# P02_Power_Management.net
KiCad netlist of a schematic drawn in Altium Designer
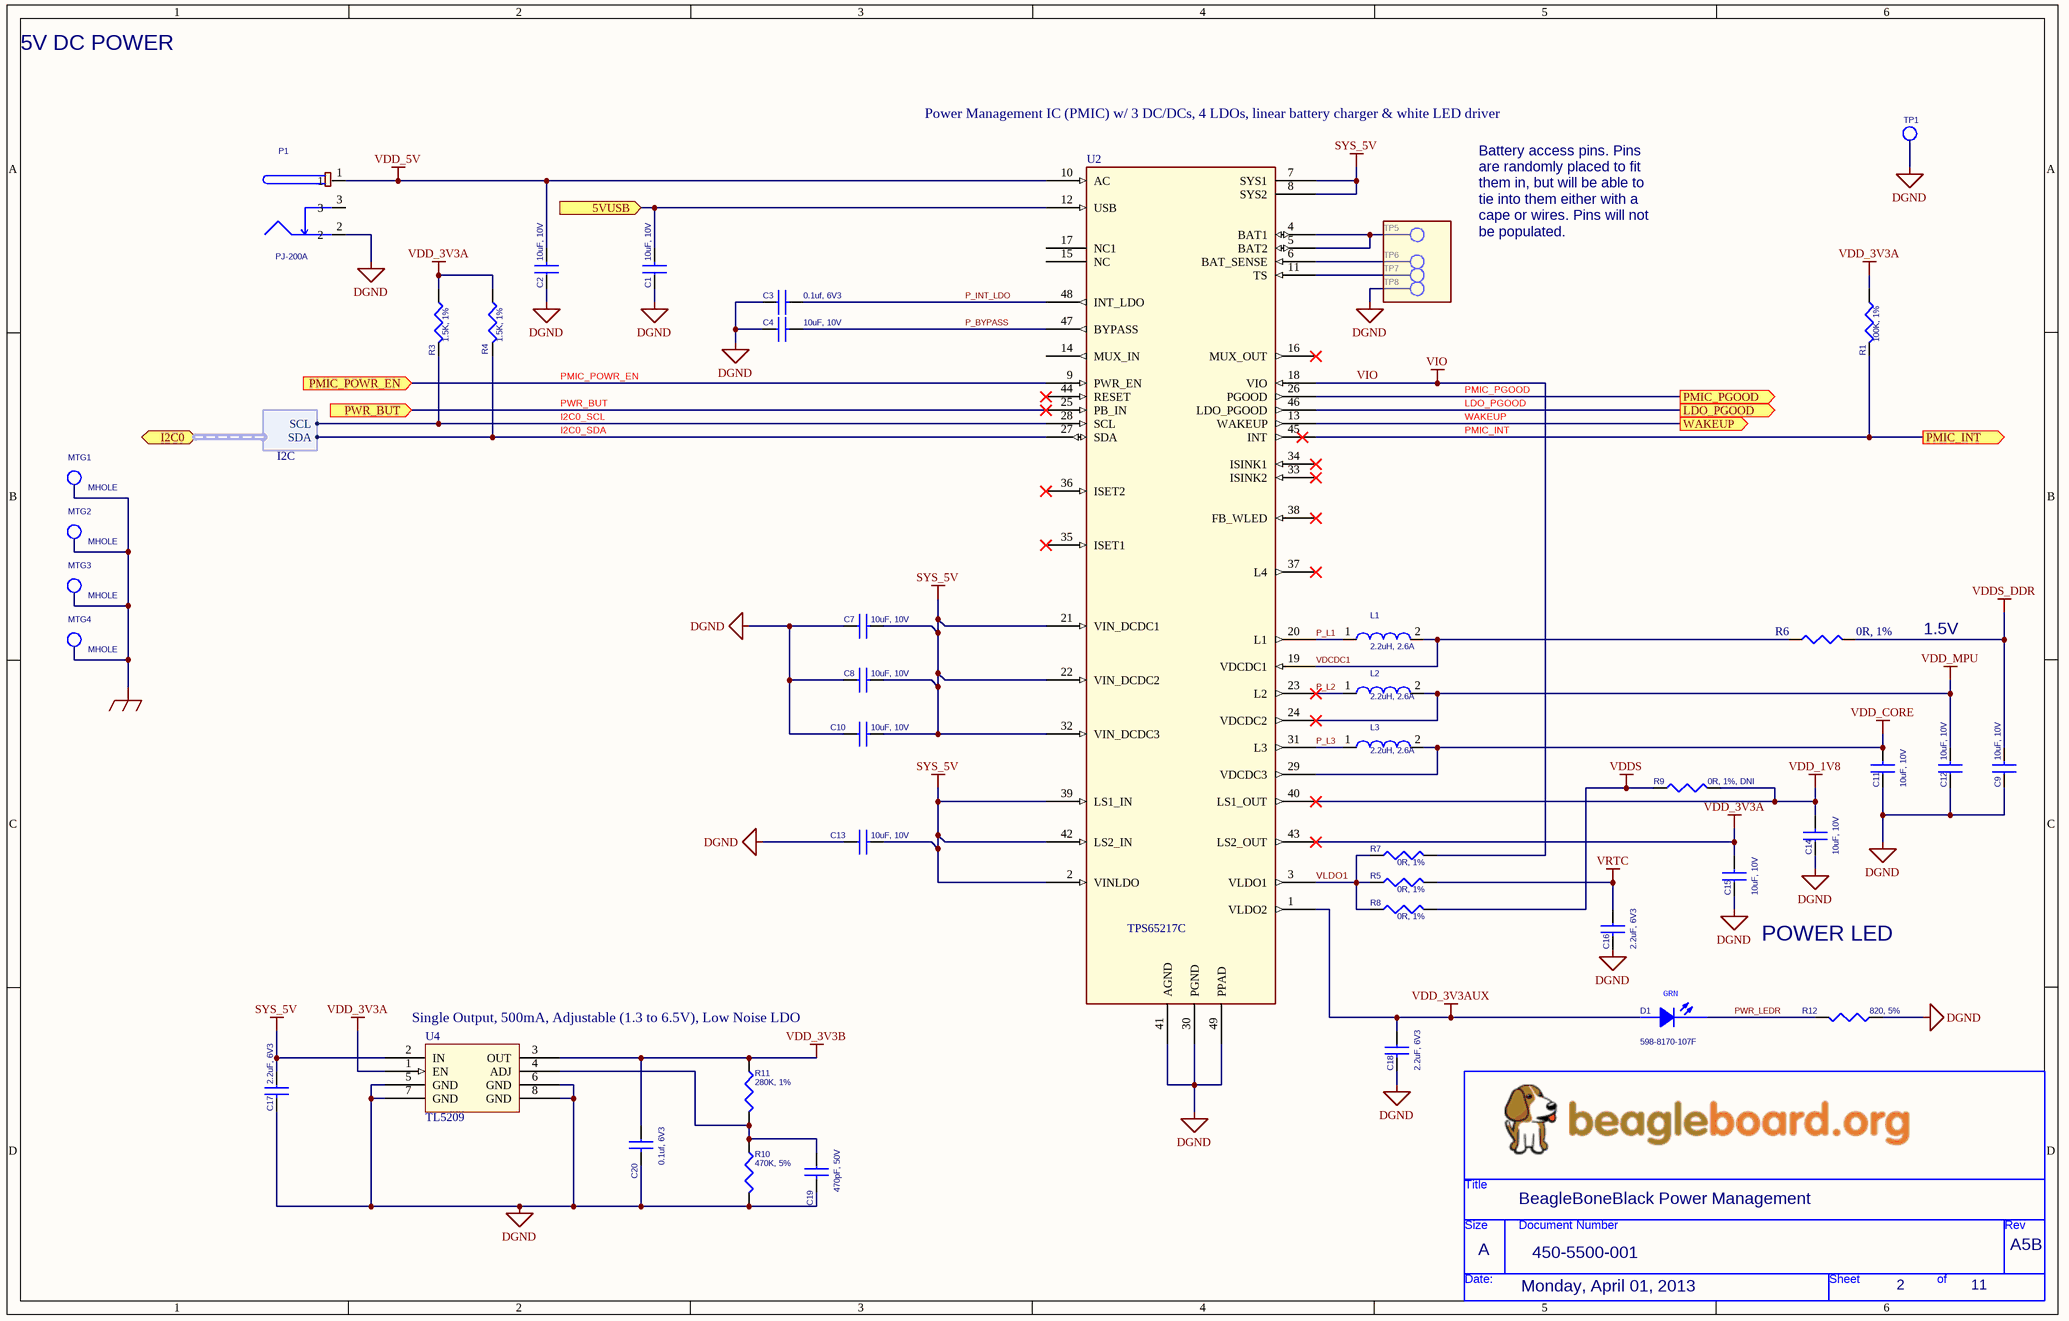
[diagram p0: P02_Power Management.SchDoc]

(export (version "E")
  (design (tool "Eeschema 10.0.6"))
  (components
    (comp (ref "C1")
      (value "10uF, 10V")
      (description "CAP CER 10UF 10V Y5V 0805")
      (fields
        (field (name "MANUFACTURER") "TDK Corporation")
        (field (name "MANUFACTURER PART NUMBER") "C2012Y5V1A106Z")
      )
      (libsource (lib "BEAGLEBONEBLACK_REV A5B") (part "CAP_4.7uF_X5R_6.3V_10%_0603"))
    )
    (comp (ref "C2")
      (value "10uF, 10V")
      (footprint "805")
      (description "CAP CER 10UF 10V Y5V 0805")
      (fields
        (field (name "MANUFACTURER") "TDK Corporation")
        (field (name "MANUFACTURER PART NUMBER") "C2012Y5V1A106Z")
      )
      (libsource (lib "BEAGLEBONEBLACK_REV A5B") (part "CAP_4.7uF_X5R_6.3V_10%_0603"))
    )
    (comp (ref "C3")
      (value "0.1uf, 6V3")
      (footprint "402")
      (description "CAP CER 0.1UF 6.3V 10% X5R 0402")
      (fields
        (field (name "MANUFACTURER") "TDK Corporation")
        (field (name "MANUFACTURER PART NUMBER") "C1005X5R0J104K050BA")
      )
      (libsource (lib "BEAGLEBONEBLACK_REV A5B") (part "CAP_10uF_Y5V_10V_10%_0805"))
    )
    (comp (ref "C4")
      (value "10uF, 10V")
      (description "CAP CER 10UF 10V Y5V 0805")
      (fields
        (field (name "MANUFACTURER") "TDK Corporation")
        (field (name "MANUFACTURER PART NUMBER") "C2012Y5V1A106Z")
      )
      (libsource (lib "BEAGLEBONEBLACK_REV A5B") (part "CAP_10uF_Y5V_10V_10%_0805"))
    )
    (comp (ref "C7")
      (value "10uF, 10V")
      (description "CAP CER 10UF 10V Y5V 0805")
      (fields
        (field (name "MANUFACTURER") "TDK Corporation")
        (field (name "MANUFACTURER PART NUMBER") "C2012Y5V1A106Z")
      )
      (libsource (lib "BEAGLEBONEBLACK_REV A5B") (part "CAP_10uF_Y5V_10V_10%_0805"))
    )
    (comp (ref "C8")
      (value "10uF, 10V")
      (description "CAP CER 10UF 10V Y5V 0805")
      (fields
        (field (name "MANUFACTURER") "TDK Corporation")
        (field (name "MANUFACTURER PART NUMBER") "C2012Y5V1A106Z")
      )
      (libsource (lib "BEAGLEBONEBLACK_REV A5B") (part "CAP_10uF_Y5V_10V_10%_0805"))
    )
    (comp (ref "C9")
      (value "10uF, 10V")
      (description "CAP CER 10UF 10V Y5V 0805")
      (fields
        (field (name "MANUFACTURER") "TDK Corporation")
        (field (name "MANUFACTURER PART NUMBER") "C2012Y5V1A106Z")
      )
      (libsource (lib "BEAGLEBONEBLACK_REV A5B") (part "CAP_10uF_Y5V_10V_10%_0805"))
    )
    (comp (ref "C10")
      (value "10uF, 10V")
      (description "CAP CER 10UF 10V Y5V 0805")
      (fields
        (field (name "MANUFACTURER") "TDK Corporation")
        (field (name "MANUFACTURER PART NUMBER") "C2012Y5V1A106Z")
      )
      (libsource (lib "BEAGLEBONEBLACK_REV A5B") (part "CAP_10uF_Y5V_10V_10%_0805"))
    )
    (comp (ref "C11")
      (value "10uF, 10V")
      (description "CAP CER 10UF 10V Y5V 0805")
      (fields
        (field (name "MANUFACTURER") "TDK Corporation")
        (field (name "MANUFACTURER PART NUMBER") "C2012Y5V1A106Z")
      )
      (libsource (lib "BEAGLEBONEBLACK_REV A5B") (part "CAP_10uF_Y5V_10V_10%_0805"))
    )
    (comp (ref "C12")
      (value "10uF, 10V")
      (description "CAP CER 10UF 10V Y5V 0805")
      (fields
        (field (name "MANUFACTURER") "TDK Corporation")
        (field (name "MANUFACTURER PART NUMBER") "C2012Y5V1A106Z")
      )
      (libsource (lib "BEAGLEBONEBLACK_REV A5B") (part "CAP_10uF_Y5V_10V_10%_0805"))
    )
    (comp (ref "C13")
      (value "10uF, 10V")
      (description "CAP CER 10UF 10V Y5V 0805")
      (fields
        (field (name "MANUFACTURER") "TDK Corporation")
        (field (name "MANUFACTURER PART NUMBER") "C2012Y5V1A106Z")
      )
      (libsource (lib "BEAGLEBONEBLACK_REV A5B") (part "CAP_10uF_Y5V_10V_10%_0805"))
    )
    (comp (ref "C14")
      (value "10uF, 10V")
      (description "CAP CER 10UF 10V Y5V 0805")
      (fields
        (field (name "MANUFACTURER") "TDK Corporation")
        (field (name "MANUFACTURER PART NUMBER") "C2012Y5V1A106Z")
      )
      (libsource (lib "BEAGLEBONEBLACK_REV A5B") (part "CAP_10uF_Y5V_10V_10%_0805"))
    )
    (comp (ref "C15")
      (value "10uF, 10V")
      (description "CAP CER 10UF 10V Y5V 0805")
      (fields
        (field (name "MANUFACTURER") "TDK Corporation")
        (field (name "MANUFACTURER PART NUMBER") "C2012Y5V1A106Z")
      )
      (libsource (lib "BEAGLEBONEBLACK_REV A5B") (part "CAP_10uF_Y5V_10V_10%_0805"))
    )
    (comp (ref "C16")
      (value "2.2uF, 6V3")
      (footprint "402")
      (description "CAP CER 2.2UF 6.3V 10% X5R 0402")
      (fields
        (field (name "MANUFACTURER") "TDK Corporation")
        (field (name "MANUFACTURER PART NUMBER") "C1005X5R0J225K050BC")
      )
      (libsource (lib "BEAGLEBONEBLACK_REV A5B") (part "CAP_2.2uF_X5R_6.3V_10%_0402"))
    )
    (comp (ref "C17")
      (value "2.2uF, 6V3")
      (footprint "402")
      (description "CAP CER 2.2UF 6.3V 10% X5R 0402")
      (fields
        (field (name "MANUFACTURER") "TDK Corporation")
        (field (name "MANUFACTURER PART NUMBER") "C1005X5R0J225K050BC")
      )
      (libsource (lib "BEAGLEBONEBLACK_REV A5B") (part "CAP_2.2uF_X5R_6.3V_10%_0402"))
    )
    (comp (ref "C18")
      (value "2.2uF, 6V3")
      (footprint "402")
      (description "CAP CER 2.2UF 6.3V 10% X5R 0402")
      (fields
        (field (name "MANUFACTURER") "TDK Corporation")
        (field (name "MANUFACTURER PART NUMBER") "C1005X5R0J225K050BC")
      )
      (libsource (lib "BEAGLEBONEBLACK_REV A5B") (part "CAP_2.2uF_X5R_6.3V_10%_0402"))
    )
    (comp (ref "C19")
      (value "470pF, 50V")
      (footprint "402")
      (description "CAP CER 470PF 50V 10% X7R 0402")
      (fields
        (field (name "MANUFACTURER") "Murata Electronics North America")
        (field (name "MANUFACTURER PART NUMBER") "GRM155R71H471KA01D")
      )
      (libsource (lib "BEAGLEBONEBLACK_REV A5B") (part "CAP_2.2uF_X5R_6.3V_10%_0402"))
    )
    (comp (ref "C20")
      (value "0.1uf, 6V3")
      (footprint "402")
      (description "CAP CER 0.1UF 6.3V 10% X5R 0402")
      (fields
        (field (name "MANUFACTURER") "TDK Corporation")
        (field (name "MANUFACTURER PART NUMBER") "C1005X5R0J104K050BA")
      )
      (libsource (lib "BEAGLEBONEBLACK_REV A5B") (part "CAP_0.1uF_X7R_16V_10% 0402"))
    )
    (comp (ref "D1")
      (value "598-8170-107F")
      (footprint "LED_0603")
      (description "LED GREEN CLEAR 0805 SMD")
      (fields
        (field (name "MANUFACTURER") "Lite-On Inc")
        (field (name "MANUFACTURER PART NUMBER") "LTST-C170KGKT")
      )
      (libsource (lib "BEAGLEBONEBLACK_REV A5B") (part "LED_LTST-C150GKT"))
    )
    (comp (ref "L1")
      (value "2.2uH, 2.6A")
      (footprint "2520")
      (description "Inductor 2.2uH smt 2.6A, 58 milliohm")
      (fields
        (field (name "MANUFACTURER") "Murata Electronics North America")
        (field (name "MANUFACTURER PART NUMBER") "LQM2HPN2R2MG0L")
      )
      (libsource (lib "BEAGLEBONEBLACK_REV A5B") (part "IND_2.2uH_2.6A_10%_SMD"))
    )
    (comp (ref "L2")
      (value "2.2uH, 2.6A")
      (footprint "2520")
      (description "INDUCTOR 2.2UH 20% 1300MA 1008")
      (fields (field (name "MFR") "TDK") (field (name "TIINTPARTNUMBER") "1L0025"))
      (libsource (lib "BEAGLEBONEBLACK_REV A5B") (part "IND_2.2uH_2.6A_10%_SMD"))
    )
    (comp (ref "L3")
      (value "2.2uH, 2.6A")
      (footprint "2520")
      (description "INDUCTOR 2.2UH 20% 1300MA 1008")
      (fields (field (name "MFR") "TDK") (field (name "TIINTPARTNUMBER") "1L0025"))
      (libsource (lib "BEAGLEBONEBLACK_REV A5B") (part "IND_2.2uH_2.6A_10%_SMD"))
    )
    (comp (ref "MTG1")
      (value "MHOLE")
      (footprint "MTGH200C125D_PL")
      (libsource (lib "BEAGLEBONEBLACK_REV A5B") (part "MHOLE"))
    )
    (comp (ref "MTG2")
      (value "MHOLE")
      (footprint "MTGH200C125D_PL")
      (libsource (lib "BEAGLEBONEBLACK_REV A5B") (part "MHOLE"))
    )
    (comp (ref "MTG3")
      (value "MHOLE")
      (footprint "MTGH200C125D_PL")
      (libsource (lib "BEAGLEBONEBLACK_REV A5B") (part "MHOLE"))
    )
    (comp (ref "MTG4")
      (value "MHOLE")
      (footprint "MTGH200C125D_PL")
      (libsource (lib "BEAGLEBONEBLACK_REV A5B") (part "MHOLE"))
    )
    (comp (ref "P1")
      (value "PJ-200A")
      (description "CONN PWR JACK 2.1X5.5MM HIGH CUR")
      (fields (field (name "MANUFACTURER") "CUI Inc") (field (name "MANUFACTURER PART NUMBER") "PJ-002AH"))
      (libsource (lib "BEAGLEBONEBLACK_REV A5B") (part "Power_Jack"))
    )
    (comp (ref "R1")
      (value "100K, 1%")
      (footprint "402")
      (description "RES 100K OHM 1/16W 1% 0402 SMD")
      (fields
        (field (name "MANUFACTURER") "Stackpole Electronics Inc")
        (field (name "MANUFACTURER PART NUMBER") "RMCF0402FT100K")
      )
      (libsource (lib "BEAGLEBONEBLACK_REV A5B") (part "RES_100K_1/16W_1%_0402"))
    )
    (comp (ref "R3")
      (value "1.5K, 1%")
      (footprint "402")
      (description "RES 1.50K OHM 1/16W 1% 0402 SMD")
      (fields
        (field (name "MANUFACTURER") "Yageo")
        (field (name "MANUFACTURER PART NUMBER") "RC0402FR-071K5L")
      )
      (libsource (lib "BEAGLEBONEBLACK_REV A5B") (part "RES_1.5K_1/16W_5%_0402"))
    )
    (comp (ref "R4")
      (value "1.5K, 1%")
      (footprint "402")
      (description "RES 1.50K OHM 1/16W 1% 0402 SMD")
      (fields
        (field (name "MANUFACTURER") "Yageo")
        (field (name "MANUFACTURER PART NUMBER") "RC0402FR-071K5L")
      )
      (libsource (lib "BEAGLEBONEBLACK_REV A5B") (part "RES_1.5K_1/16W_5%_0402"))
    )
    (comp (ref "R5")
      (value "0R, 1%")
      (footprint "402")
      (description "RES 0.0 OHM 1/16W 0402 SMD")
      (fields
        (field (name "MANUFACTURER") "Yageo")
        (field (name "MANUFACTURER PART NUMBER") "RC0402JR-070RL")
      )
      (libsource (lib "BEAGLEBONEBLACK_REV A5B") (part "RES_0_1/16W_1%_0402"))
    )
    (comp (ref "R6")
      (value "0R, 1%")
      (footprint "402")
      (description "RES 0.0 OHM 1/16W 0402 SMD")
      (fields
        (field (name "MANUFACTURER") "Yageo")
        (field (name "MANUFACTURER PART NUMBER") "RC0402JR-070RL")
      )
      (libsource (lib "BEAGLEBONEBLACK_REV A5B") (part "RES_0_1/16W_1%_0402"))
    )
    (comp (ref "R7")
      (value "0R, 1%")
      (footprint "402")
      (description "RES 0.0 OHM 1/16W 0402 SMD")
      (fields
        (field (name "MANUFACTURER") "Yageo")
        (field (name "MANUFACTURER PART NUMBER") "RC0402JR-070RL")
      )
      (libsource (lib "BEAGLEBONEBLACK_REV A5B") (part "RES_0_1/16W_1%_0402"))
    )
    (comp (ref "R8")
      (value "0R, 1%")
      (footprint "402")
      (description "RES 0.0 OHM 1/16W 0402 SMD")
      (fields
        (field (name "MANUFACTURER") "Yageo")
        (field (name "MANUFACTURER PART NUMBER") "RC0402JR-070RL")
      )
      (libsource (lib "BEAGLEBONEBLACK_REV A5B") (part "RES_0_1/16W_1%_0402"))
    )
    (comp (ref "R9")
      (value "0R, 1%, DNI")
      (footprint "402")
      (description "RES 0.0 OHM 1/16W 0402 SMD")
      (fields
        (field (name "MANUFACTURER") "Yageo")
        (field (name "MANUFACTURER PART NUMBER") "RC0402JR-070RL")
      )
      (libsource (lib "BEAGLEBONEBLACK_REV A5B") (part "RES_0_1/16W_1%_0402"))
    )
    (comp (ref "R10")
      (value "470K, 5%")
      (footprint "402")
      (description "RES 470K OHM 1/16W 1% 0402 SMD")
      (fields
        (field (name "MANUFACTURER") "Yageo")
        (field (name "MANUFACTURER PART NUMBER") "RC0402FR-07470KL")
      )
      (libsource (lib "BEAGLEBONEBLACK_REV A5B") (part "RES_470_1/10W_5%_0402"))
    )
    (comp (ref "R11")
      (value "280K, 1%")
      (footprint "402")
      (description "RES 280K OHM 1/16W 1% 0402 SMD")
      (fields
        (field (name "MANUFACTURER") "Stackpole Electronics Inc")
        (field (name "MANUFACTURER PART NUMBER") "RMCF0402FT280K")
      )
      (libsource (lib "BEAGLEBONEBLACK_REV A5B") (part "RES_470_1/10W_5%_0402"))
    )
    (comp (ref "R12")
      (value "820, 5%")
      (footprint "402")
      (description "RES 820 OHM 1/10W 5% 0402 SMD")
      (fields
        (field (name "MANUFACTURER") "Yageo")
        (field (name "MANUFACTURER PART NUMBER") "RC0402JR-07820RL")
      )
      (libsource (lib "BEAGLEBONEBLACK_REV A5B") (part "RES_470_1/10W_5%_0402"))
    )
    (comp (ref "TP1")
      (value "TESTPT1")
      (footprint "tp1-8040")
      (libsource (lib "BEAGLEBONEBLACK_REV A5B") (part "TESTPT1"))
    )
    (comp (ref "TP5")
      (value "TESTPT1")
      (footprint "TP60C33D")
      (libsource (lib "BEAGLEBONEBLACK_REV A5B") (part "TESTPT1"))
    )
    (comp (ref "TP6")
      (value "TESTPT1")
      (footprint "TP60C33D")
      (libsource (lib "BEAGLEBONEBLACK_REV A5B") (part "TESTPT1"))
    )
    (comp (ref "TP7")
      (value "TESTPT1")
      (footprint "TP60C33D")
      (libsource (lib "BEAGLEBONEBLACK_REV A5B") (part "TESTPT1"))
    )
    (comp (ref "TP8")
      (value "TESTPT1")
      (footprint "TP60C33D")
      (libsource (lib "BEAGLEBONEBLACK_REV A5B") (part "TESTPT1"))
    )
    (comp (ref "U2")
      (value "TPS65217C")
      (footprint "U_48_RSL")
      (description "IC PMIC BATT PWR SYST 48VQFN")
      (fields
        (field (name "MANUFACTURER") "Texas Instruments")
        (field (name "MANUFACTURER PART NUMBER") "TPS65217CRSLR")
      )
      (libsource (lib "BEAGLEBONEBLACK_REV A5B") (part "PWR_TPS65217_2"))
    )
    (comp (ref "U4")
      (value "TL5209")
      (footprint "SO8-25X75")
      (description "IC LDO VOLT REG 500MA 8-SOIC")
      (fields
        (field (name "MANUFACTURER") "Texas Instruments")
        (field (name "MANUFACTURER PART NUMBER") "TL5209DR")
      )
      (libsource (lib "BEAGLEBONEBLACK_REV A5B") (part "TL5209"))
    )
  )
  (nets
    (net (code "2") (name "/5VUSB") (class "Default")
      (node (ref "C1") (pin "2") (pinfunction "2_2") (pintype "passive"))
      (node (ref "U2") (pin "12") (pinfunction "USB_12") (pintype "input"))
    )
    (net (code "3") (name "/I2C0_SCL") (class "Default")
      (node (ref "R3") (pin "2") (pinfunction "2_2") (pintype "passive"))
      (node (ref "U2") (pin "28") (pinfunction "SCL_28") (pintype "input"))
    )
    (net (code "4") (name "/I2C0_SDA") (class "Default")
      (node (ref "R4") (pin "2") (pinfunction "2_2") (pintype "passive"))
      (node (ref "U2") (pin "27") (pinfunction "SDA_27") (pintype "bidirectional"))
    )
    (net (code "5") (name "/LDO_PGOOD") (class "Default")
      (node (ref "U2") (pin "46") (pinfunction "LDO_PGOOD_46") (pintype "output"))
    )
    (net (code "6") (name "/PMIC_INT") (class "Default")
      (node (ref "R1") (pin "2") (pinfunction "2_2") (pintype "passive"))
      (node (ref "U2") (pin "45") (pinfunction "INT_45") (pintype "output"))
    )
    (net (code "7") (name "/PMIC_PGOOD") (class "Default")
      (node (ref "U2") (pin "26") (pinfunction "PGOOD_26") (pintype "output"))
    )
    (net (code "8") (name "/PMIC_POWR_EN") (class "Default")
      (node (ref "U2") (pin "9") (pinfunction "PWR_EN_9") (pintype "input"))
    )
    (net (code "9") (name "/PWR_BUT") (class "Default")
      (node (ref "U2") (pin "25") (pinfunction "PB_IN_25") (pintype "input+no_connect"))
    )
    (net (code "10") (name "/PWR_LEDR") (class "Default")
      (node (ref "D1") (pin "1") (pinfunction "C_1") (pintype "passive"))
      (node (ref "R12") (pin "2") (pinfunction "2_2") (pintype "passive"))
    )
    (net (code "11") (name "/P_BYPASS") (class "Default")
      (node (ref "C4") (pin "2") (pinfunction "2_2") (pintype "passive"))
      (node (ref "U2") (pin "47") (pinfunction "BYPASS_47") (pintype "output"))
    )
    (net (code "12") (name "/P_INT_LDO") (class "Default")
      (node (ref "C3") (pin "2") (pinfunction "2_2") (pintype "passive"))
      (node (ref "U2") (pin "48") (pinfunction "INT_LDO_48") (pintype "output"))
    )
    (net (code "13") (name "/P_L1") (class "Default")
      (node (ref "L1") (pin "1") (pinfunction "1_1") (pintype "passive"))
      (node (ref "U2") (pin "20") (pinfunction "L1_20") (pintype "output"))
    )
    (net (code "14") (name "/P_L2") (class "Default")
      (node (ref "L2") (pin "1") (pinfunction "1_1") (pintype "passive"))
      (node (ref "U2") (pin "23") (pinfunction "L2_23") (pintype "output"))
    )
    (net (code "15") (name "/P_L3") (class "Default")
      (node (ref "L3") (pin "1") (pinfunction "1_1") (pintype "passive"))
      (node (ref "U2") (pin "31") (pinfunction "L3_31") (pintype "output"))
    )
    (net (code "16") (name "/VDCDC1") (class "Default")
      (node (ref "L1") (pin "2") (pinfunction "2_2") (pintype "passive"))
      (node (ref "R6") (pin "1") (pinfunction "1_1") (pintype "passive"))
      (node (ref "U2") (pin "19") (pinfunction "VDCDC1_19") (pintype "input"))
    )
    (net (code "17") (name "/VLDO1") (class "Default")
      (node (ref "R5") (pin "1") (pinfunction "1_1") (pintype "passive"))
      (node (ref "R7") (pin "1") (pinfunction "1_1") (pintype "passive"))
      (node (ref "R8") (pin "1") (pinfunction "1_1") (pintype "passive"))
      (node (ref "U2") (pin "3") (pinfunction "VLDO1_3") (pintype "output"))
    )
    (net (code "18") (name "/WAKEUP") (class "Default")
      (node (ref "U2") (pin "13") (pinfunction "WAKEUP_13") (pintype "output"))
    )
    (net (code "20") (name "DGND") (class "Default")
      (node (ref "C1") (pin "1") (pinfunction "1_1") (pintype "passive"))
      (node (ref "C10") (pin "1") (pinfunction "1_1") (pintype "passive"))
      (node (ref "C11") (pin "1") (pinfunction "1_1") (pintype "passive"))
      (node (ref "C12") (pin "1") (pinfunction "1_1") (pintype "passive"))
      (node (ref "C13") (pin "1") (pinfunction "1_1") (pintype "passive"))
      (node (ref "C14") (pin "1") (pinfunction "1_1") (pintype "passive"))
      (node (ref "C15") (pin "1") (pinfunction "1_1") (pintype "passive"))
      (node (ref "C16") (pin "2") (pinfunction "2_2") (pintype "passive"))
      (node (ref "C17") (pin "2") (pinfunction "2_2") (pintype "passive"))
      (node (ref "C18") (pin "2") (pinfunction "2_2") (pintype "passive"))
      (node (ref "C19") (pin "2") (pinfunction "2_2") (pintype "passive"))
      (node (ref "C2") (pin "1") (pinfunction "1_1") (pintype "passive"))
      (node (ref "C20") (pin "2") (pinfunction "2_2") (pintype "passive"))
      (node (ref "C3") (pin "1") (pinfunction "1_1") (pintype "passive"))
      (node (ref "C4") (pin "1") (pinfunction "1_1") (pintype "passive"))
      (node (ref "C7") (pin "1") (pinfunction "1_1") (pintype "passive"))
      (node (ref "C8") (pin "1") (pinfunction "1_1") (pintype "passive"))
      (node (ref "C9") (pin "1") (pinfunction "1_1") (pintype "passive"))
      (node (ref "P1") (pin "2") (pinfunction "2_2") (pintype "passive"))
      (node (ref "R10") (pin "2") (pinfunction "2_2") (pintype "passive"))
      (node (ref "R12") (pin "1") (pinfunction "1_1") (pintype "passive"))
      (node (ref "TP1") (pin "1") (pinfunction "TP_1") (pintype "passive"))
      (node (ref "TP8") (pin "1") (pinfunction "TP_1") (pintype "passive"))
      (node (ref "U2") (pin "30") (pinfunction "PGND_30") (pintype "power_in"))
      (node (ref "U2") (pin "41") (pinfunction "AGND_41") (pintype "power_in"))
      (node (ref "U2") (pin "49") (pinfunction "PPAD_49") (pintype "power_in"))
      (node (ref "U4") (pin "5") (pinfunction "GND_5") (pintype "power_in"))
      (node (ref "U4") (pin "6") (pinfunction "GND_6") (pintype "power_in"))
      (node (ref "U4") (pin "7") (pinfunction "GND_7") (pintype "power_in"))
      (node (ref "U4") (pin "8") (pinfunction "GND_8") (pintype "power_in"))
    )
    (net (code "21") (name "GND_EARTH") (class "Default")
      (node (ref "MTG1") (pin "1") (pinfunction "TP_1") (pintype "passive"))
      (node (ref "MTG2") (pin "1") (pinfunction "TP_1") (pintype "passive"))
      (node (ref "MTG3") (pin "1") (pinfunction "TP_1") (pintype "passive"))
      (node (ref "MTG4") (pin "1") (pinfunction "TP_1") (pintype "passive"))
    )
    (net (code "22") (name "Net-(TP5-TP)") (class "Default")
      (node (ref "TP5") (pin "1") (pinfunction "TP_1") (pintype "passive"))
      (node (ref "U2") (pin "4") (pinfunction "BAT1_4") (pintype "bidirectional"))
      (node (ref "U2") (pin "5") (pinfunction "BAT2_5") (pintype "bidirectional"))
    )
    (net (code "23") (name "Net-(TP6-TP)") (class "Default")
      (node (ref "TP6") (pin "1") (pinfunction "TP_1") (pintype "passive"))
      (node (ref "U2") (pin "6") (pinfunction "BAT_SENSE_6") (pintype "input"))
    )
    (net (code "24") (name "Net-(TP7-TP)") (class "Default")
      (node (ref "TP7") (pin "1") (pinfunction "TP_1") (pintype "passive"))
      (node (ref "U2") (pin "11") (pinfunction "TS_11") (pintype "input"))
    )
    (net (code "25") (name "Net-(U4-ADJ)") (class "Default")
      (node (ref "C19") (pin "1") (pinfunction "1_1") (pintype "passive"))
      (node (ref "R10") (pin "1") (pinfunction "1_1") (pintype "passive"))
      (node (ref "R11") (pin "2") (pinfunction "2_2") (pintype "passive"))
      (node (ref "U4") (pin "4") (pinfunction "ADJ_4") (pintype "passive"))
    )
    (net (code "26") (name "SYS_5V") (class "Default")
      (node (ref "C10") (pin "2") (pinfunction "2_2") (pintype "passive"))
      (node (ref "C13") (pin "2") (pinfunction "2_2") (pintype "passive"))
      (node (ref "C17") (pin "1") (pinfunction "1_1") (pintype "passive"))
      (node (ref "C7") (pin "2") (pinfunction "2_2") (pintype "passive"))
      (node (ref "C8") (pin "2") (pinfunction "2_2") (pintype "passive"))
      (node (ref "U2") (pin "2") (pinfunction "VINLDO_2") (pintype "input"))
      (node (ref "U2") (pin "21") (pinfunction "VIN_DCDC1_21") (pintype "input"))
      (node (ref "U2") (pin "22") (pinfunction "VIN_DCDC2_22") (pintype "input"))
      (node (ref "U2") (pin "32") (pinfunction "VIN_DCDC3_32") (pintype "input"))
      (node (ref "U2") (pin "39") (pinfunction "LS1_IN_39") (pintype "input"))
      (node (ref "U2") (pin "42") (pinfunction "LS2_IN_42") (pintype "input"))
      (node (ref "U2") (pin "7") (pinfunction "SYS1_7") (pintype "passive"))
      (node (ref "U2") (pin "8") (pinfunction "SYS2_8") (pintype "passive"))
      (node (ref "U4") (pin "2") (pinfunction "IN_2") (pintype "power_in"))
    )
    (net (code "27") (name "VDDS") (class "Default")
      (node (ref "R8") (pin "2") (pinfunction "2_2") (pintype "passive"))
      (node (ref "R9") (pin "1") (pinfunction "1_1") (pintype "passive"))
    )
    (net (code "28") (name "VDDS_DDR") (class "Default")
      (node (ref "C9") (pin "2") (pinfunction "2_2") (pintype "passive"))
      (node (ref "R6") (pin "2") (pinfunction "2_2") (pintype "passive"))
    )
    (net (code "29") (name "VDD_1V8") (class "Default")
      (node (ref "C14") (pin "2") (pinfunction "2_2") (pintype "passive"))
      (node (ref "R9") (pin "2") (pinfunction "2_2") (pintype "passive"))
      (node (ref "U2") (pin "40") (pinfunction "LS1_OUT_40") (pintype "output"))
    )
    (net (code "30") (name "VDD_3V3A") (class "Default")
      (node (ref "C15") (pin "2") (pinfunction "2_2") (pintype "passive"))
      (node (ref "R1") (pin "1") (pinfunction "1_1") (pintype "passive"))
      (node (ref "R3") (pin "1") (pinfunction "1_1") (pintype "passive"))
      (node (ref "R4") (pin "1") (pinfunction "1_1") (pintype "passive"))
      (node (ref "U2") (pin "43") (pinfunction "LS2_OUT_43") (pintype "output"))
      (node (ref "U4") (pin "1") (pinfunction "EN_1") (pintype "input"))
    )
    (net (code "31") (name "VDD_3V3AUX") (class "Default")
      (node (ref "C18") (pin "1") (pinfunction "1_1") (pintype "passive"))
      (node (ref "D1") (pin "2") (pinfunction "A_2") (pintype "passive"))
      (node (ref "U2") (pin "1") (pinfunction "VLDO2_1") (pintype "output"))
    )
    (net (code "32") (name "VDD_3V3B") (class "Default")
      (node (ref "C20") (pin "1") (pinfunction "1_1") (pintype "passive"))
      (node (ref "R11") (pin "1") (pinfunction "1_1") (pintype "passive"))
      (node (ref "U4") (pin "3") (pinfunction "OUT_3") (pintype "power_in"))
    )
    (net (code "33") (name "VDD_5V") (class "Default")
      (node (ref "C2") (pin "2") (pinfunction "2_2") (pintype "passive"))
      (node (ref "P1") (pin "1") (pinfunction "1_1") (pintype "passive"))
      (node (ref "U2") (pin "10") (pinfunction "AC_10") (pintype "input"))
    )
    (net (code "34") (name "VDD_CORE") (class "Default")
      (node (ref "C11") (pin "2") (pinfunction "2_2") (pintype "passive"))
      (node (ref "L3") (pin "2") (pinfunction "2_2") (pintype "passive"))
      (node (ref "U2") (pin "29") (pinfunction "VDCDC3_29") (pintype "output"))
    )
    (net (code "35") (name "VDD_MPU") (class "Default")
      (node (ref "C12") (pin "2") (pinfunction "2_2") (pintype "passive"))
      (node (ref "L2") (pin "2") (pinfunction "2_2") (pintype "passive"))
      (node (ref "U2") (pin "24") (pinfunction "VDCDC2_24") (pintype "output"))
    )
    (net (code "36") (name "VIO") (class "Default")
      (node (ref "R7") (pin "2") (pinfunction "2_2") (pintype "passive"))
      (node (ref "U2") (pin "18") (pinfunction "VIO_18") (pintype "input"))
    )
    (net (code "37") (name "VRTC") (class "Default")
      (node (ref "C16") (pin "1") (pinfunction "1_1") (pintype "passive"))
      (node (ref "R5") (pin "2") (pinfunction "2_2") (pintype "passive"))
    )
    (net (code "38") (name "unconnected-(P1-Pad3)") (class "Default")
      (node (ref "P1") (pin "3") (pinfunction "3_3") (pintype "passive"))
    )
    (net (code "39") (name "unconnected-(U2-FB_WLED-Pad38)") (class "Default")
      (node (ref "U2") (pin "38") (pinfunction "FB_WLED_38") (pintype "input+no_connect"))
    )
    (net (code "40") (name "unconnected-(U2-ISET1-Pad35)") (class "Default")
      (node (ref "U2") (pin "35") (pinfunction "ISET1_35") (pintype "input+no_connect"))
    )
    (net (code "41") (name "unconnected-(U2-ISET2-Pad36)") (class "Default")
      (node (ref "U2") (pin "36") (pinfunction "ISET2_36") (pintype "input+no_connect"))
    )
    (net (code "42") (name "unconnected-(U2-ISINK1-Pad34)") (class "Default")
      (node (ref "U2") (pin "34") (pinfunction "ISINK1_34") (pintype "input+no_connect"))
    )
    (net (code "43") (name "unconnected-(U2-ISINK2-Pad33)") (class "Default")
      (node (ref "U2") (pin "33") (pinfunction "ISINK2_33") (pintype "input+no_connect"))
    )
    (net (code "44") (name "unconnected-(U2-L4-Pad37)") (class "Default")
      (node (ref "U2") (pin "37") (pinfunction "L4_37") (pintype "output+no_connect"))
    )
    (net (code "45") (name "unconnected-(U2-MUX_IN-Pad14)") (class "Default")
      (node (ref "U2") (pin "14") (pinfunction "MUX_IN_14") (pintype "output"))
    )
    (net (code "46") (name "unconnected-(U2-MUX_OUT-Pad16)") (class "Default")
      (node (ref "U2") (pin "16") (pinfunction "MUX_OUT_16") (pintype "output+no_connect"))
    )
    (net (code "47") (name "unconnected-(U2-NC-Pad15)") (class "Default")
      (node (ref "U2") (pin "15") (pinfunction "NC_15") (pintype "passive"))
    )
    (net (code "48") (name "unconnected-(U2-NC1-Pad17)") (class "Default")
      (node (ref "U2") (pin "17") (pinfunction "NC1_17") (pintype "passive"))
    )
    (net (code "49") (name "unconnected-(U2-RESET-Pad44)") (class "Default")
      (node (ref "U2") (pin "44") (pinfunction "RESET_44") (pintype "input+no_connect"))
    )
  )
)
